# Caps.net
KiCad netlist of a schematic drawn in Altium Designer
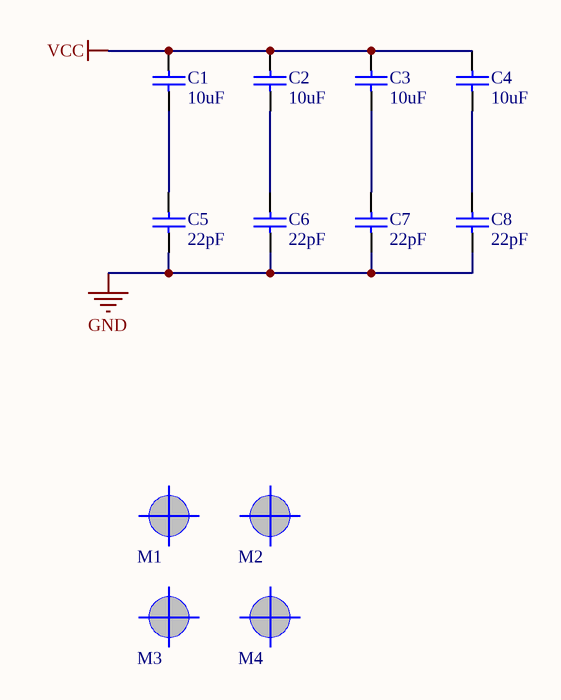
[diagram p0: Caps.SchDoc]

(export (version "E")
  (design (tool "Eeschema 10.0.6"))
  (components
    (comp (ref "C1")
      (value "10uF")
      (footprint "CAP-1206")
      (description "Capacitor")
      (fields (field (name "PUBLISHER") "Altium Limited"))
      (libsource (lib "Miscellaneous Devices") (part "Cap"))
    )
    (comp (ref "C2")
      (value "10uF")
      (footprint "CAP-1206")
      (description "Capacitor")
      (fields (field (name "PUBLISHER") "Altium Limited"))
      (libsource (lib "Miscellaneous Devices") (part "Cap"))
    )
    (comp (ref "C3")
      (value "10uF")
      (footprint "CAP-1206")
      (description "Capacitor")
      (fields (field (name "PUBLISHER") "Altium Limited"))
      (libsource (lib "Miscellaneous Devices") (part "Cap"))
    )
    (comp (ref "C4")
      (value "10uF")
      (footprint "CAP-1206")
      (description "Capacitor")
      (fields (field (name "PUBLISHER") "Altium Limited"))
      (libsource (lib "Miscellaneous Devices") (part "Cap"))
    )
    (comp (ref "C5")
      (value "22pF")
      (footprint "CAP-0402")
      (description "Capacitor")
      (fields (field (name "PUBLISHER") "Altium Limited"))
      (libsource (lib "Miscellaneous Devices") (part "Cap"))
    )
    (comp (ref "C6")
      (value "22pF")
      (footprint "CAP-0402")
      (description "Capacitor")
      (fields (field (name "PUBLISHER") "Altium Limited"))
      (libsource (lib "Miscellaneous Devices") (part "Cap"))
    )
    (comp (ref "C7")
      (value "22pF")
      (footprint "CAP-0402")
      (description "Capacitor")
      (fields (field (name "PUBLISHER") "Altium Limited"))
      (libsource (lib "Miscellaneous Devices") (part "Cap"))
    )
    (comp (ref "C8")
      (value "22pF")
      (footprint "CAP-0402")
      (description "Capacitor")
      (fields (field (name "PUBLISHER") "Altium Limited"))
      (libsource (lib "Miscellaneous Devices") (part "Cap"))
    )
    (comp (ref "M1")
      (value "Screw hole")
      (footprint "MECH-SCREW-M2.3")
      (libsource (lib "std") (part "Screw hole"))
    )
    (comp (ref "M2")
      (value "Screw hole")
      (footprint "MECH-SCREW-M2.3")
      (libsource (lib "std") (part "Screw hole"))
    )
    (comp (ref "M3")
      (value "Screw hole")
      (footprint "MECH-SCREW-M2.3")
      (libsource (lib "std") (part "Screw hole"))
    )
    (comp (ref "M4")
      (value "Screw hole")
      (footprint "MECH-SCREW-M2.3")
      (libsource (lib "std") (part "Screw hole"))
    )
  )
  (nets
    (net (code "1") (name "GND") (class "Default")
      (node (ref "C5") (pin "1") (pinfunction "1_1") (pintype "passive"))
      (node (ref "C6") (pin "1") (pinfunction "1_1") (pintype "passive"))
      (node (ref "C7") (pin "1") (pinfunction "1_1") (pintype "passive"))
      (node (ref "C8") (pin "1") (pinfunction "1_1") (pintype "passive"))
    )
    (net (code "2") (name "Net-(C1-Pad1)") (class "Default")
      (node (ref "C1") (pin "1") (pinfunction "1_1") (pintype "passive"))
      (node (ref "C5") (pin "2") (pinfunction "2_2") (pintype "passive"))
    )
    (net (code "3") (name "Net-(C2-Pad1)") (class "Default")
      (node (ref "C2") (pin "1") (pinfunction "1_1") (pintype "passive"))
      (node (ref "C6") (pin "2") (pinfunction "2_2") (pintype "passive"))
    )
    (net (code "4") (name "Net-(C3-Pad1)") (class "Default")
      (node (ref "C3") (pin "1") (pinfunction "1_1") (pintype "passive"))
      (node (ref "C7") (pin "2") (pinfunction "2_2") (pintype "passive"))
    )
    (net (code "5") (name "Net-(C4-Pad1)") (class "Default")
      (node (ref "C4") (pin "1") (pinfunction "1_1") (pintype "passive"))
      (node (ref "C8") (pin "2") (pinfunction "2_2") (pintype "passive"))
    )
    (net (code "6") (name "VCC") (class "Default")
      (node (ref "C1") (pin "2") (pinfunction "2_2") (pintype "passive"))
      (node (ref "C2") (pin "2") (pinfunction "2_2") (pintype "passive"))
      (node (ref "C3") (pin "2") (pinfunction "2_2") (pintype "passive"))
      (node (ref "C4") (pin "2") (pinfunction "2_2") (pintype "passive"))
    )
  )
)
